# QSPI.net
KiCad netlist of a schematic drawn in Altium Designer
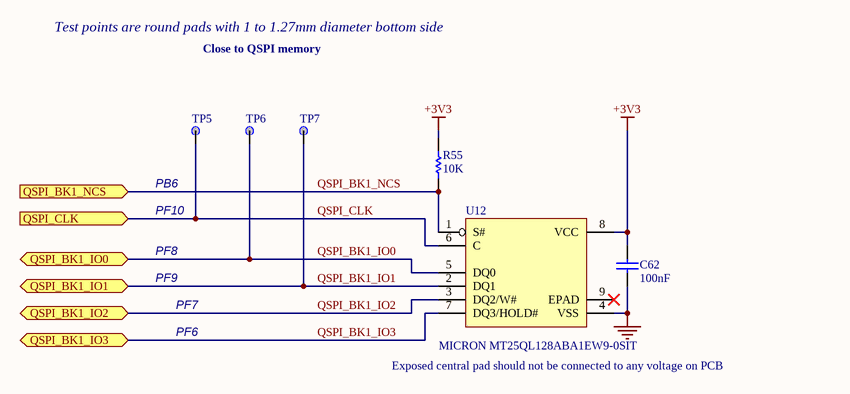
[diagram p0: QSPI.SchDoc]

(export (version "E")
  (design (tool "Eeschema 10.0.6"))
  (components
    (comp (ref "C62")
      (value "100nF")
      (footprint "0402C")
      (description "Capacitor")
      (fields (field (name "PUBLISHER") "Altium Limited"))
      (libsource (lib "Miscellaneous Devices") (part "Cap"))
    )
    (comp (ref "R55")
      (value "10K")
      (footprint "0402R")
      (description "Resistor")
      (libsource (lib "MCD_TOOLS") (part "Res_10K_1%_0402"))
    )
    (comp (ref "TP5") (value "TP") (footprint "TP_C40") (libsource (lib "Almos") (part "TP")))
    (comp (ref "TP6") (value "TP") (footprint "TP_C40") (libsource (lib "Almos") (part "TP")))
    (comp (ref "TP7") (value "TP") (footprint "TP_C40") (libsource (lib "Almos") (part "TP")))
    (comp (ref "U12")
      (value "MICRON MT25QL128ABA1EW9-0SIT")
      (footprint "ICC_W-PDFN-8_8X6_P127")
      (description "128Mb, 3V, Multiple I/O Serial Flash Memory, Quad/Dual")
      (libsource (lib "MB1189") (part "MT25QL128ABA1EW9-0SIT"))
    )
  )
  (nets
    (net (code "1") (name "+3V3") (class "Default")
      (node (ref "C62") (pin "1") (pinfunction "1_1") (pintype "passive"))
      (node (ref "R55") (pin "2") (pinfunction "2_2") (pintype "passive"))
      (node (ref "U12") (pin "8") (pinfunction "VCC_8") (pintype "passive"))
    )
    (net (code "2") (name "/QSPI_BK1_IO0") (class "Default")
      (node (ref "TP6") (pin "1") (pinfunction "1_1") (pintype "passive"))
      (node (ref "U12") (pin "5") (pinfunction "DQ0_5") (pintype "passive"))
    )
    (net (code "3") (name "/QSPI_BK1_IO1") (class "Default")
      (node (ref "TP7") (pin "1") (pinfunction "1_1") (pintype "passive"))
      (node (ref "U12") (pin "2") (pinfunction "DQ1_2") (pintype "passive"))
    )
    (net (code "4") (name "/QSPI_BK1_IO2") (class "Default")
      (node (ref "U12") (pin "3") (pinfunction "DQ2/W#_3") (pintype "passive"))
    )
    (net (code "5") (name "/QSPI_BK1_IO3") (class "Default")
      (node (ref "U12") (pin "7") (pinfunction "DQ3/HOLD#_7") (pintype "passive"))
    )
    (net (code "6") (name "/QSPI_BK1_NCS") (class "Default")
      (node (ref "R55") (pin "1") (pinfunction "1_1") (pintype "passive"))
      (node (ref "U12") (pin "1") (pinfunction "S#_1") (pintype "passive"))
    )
    (net (code "7") (name "/QSPI_CLK") (class "Default")
      (node (ref "TP5") (pin "1") (pinfunction "1_1") (pintype "passive"))
      (node (ref "U12") (pin "6") (pinfunction "C_6") (pintype "passive"))
    )
    (net (code "8") (name "GND") (class "Default")
      (node (ref "C62") (pin "2") (pinfunction "2_2") (pintype "passive"))
      (node (ref "U12") (pin "4") (pinfunction "VSS_4") (pintype "passive"))
    )
    (net (code "9") (name "unconnected-(U12-EPAD-Pad9)") (class "Default")
      (node (ref "U12") (pin "9") (pinfunction "EPAD_9") (pintype "passive+no_connect"))
    )
  )
)
